# Clock2.net
KiCad netlist of a schematic drawn in EAGLE
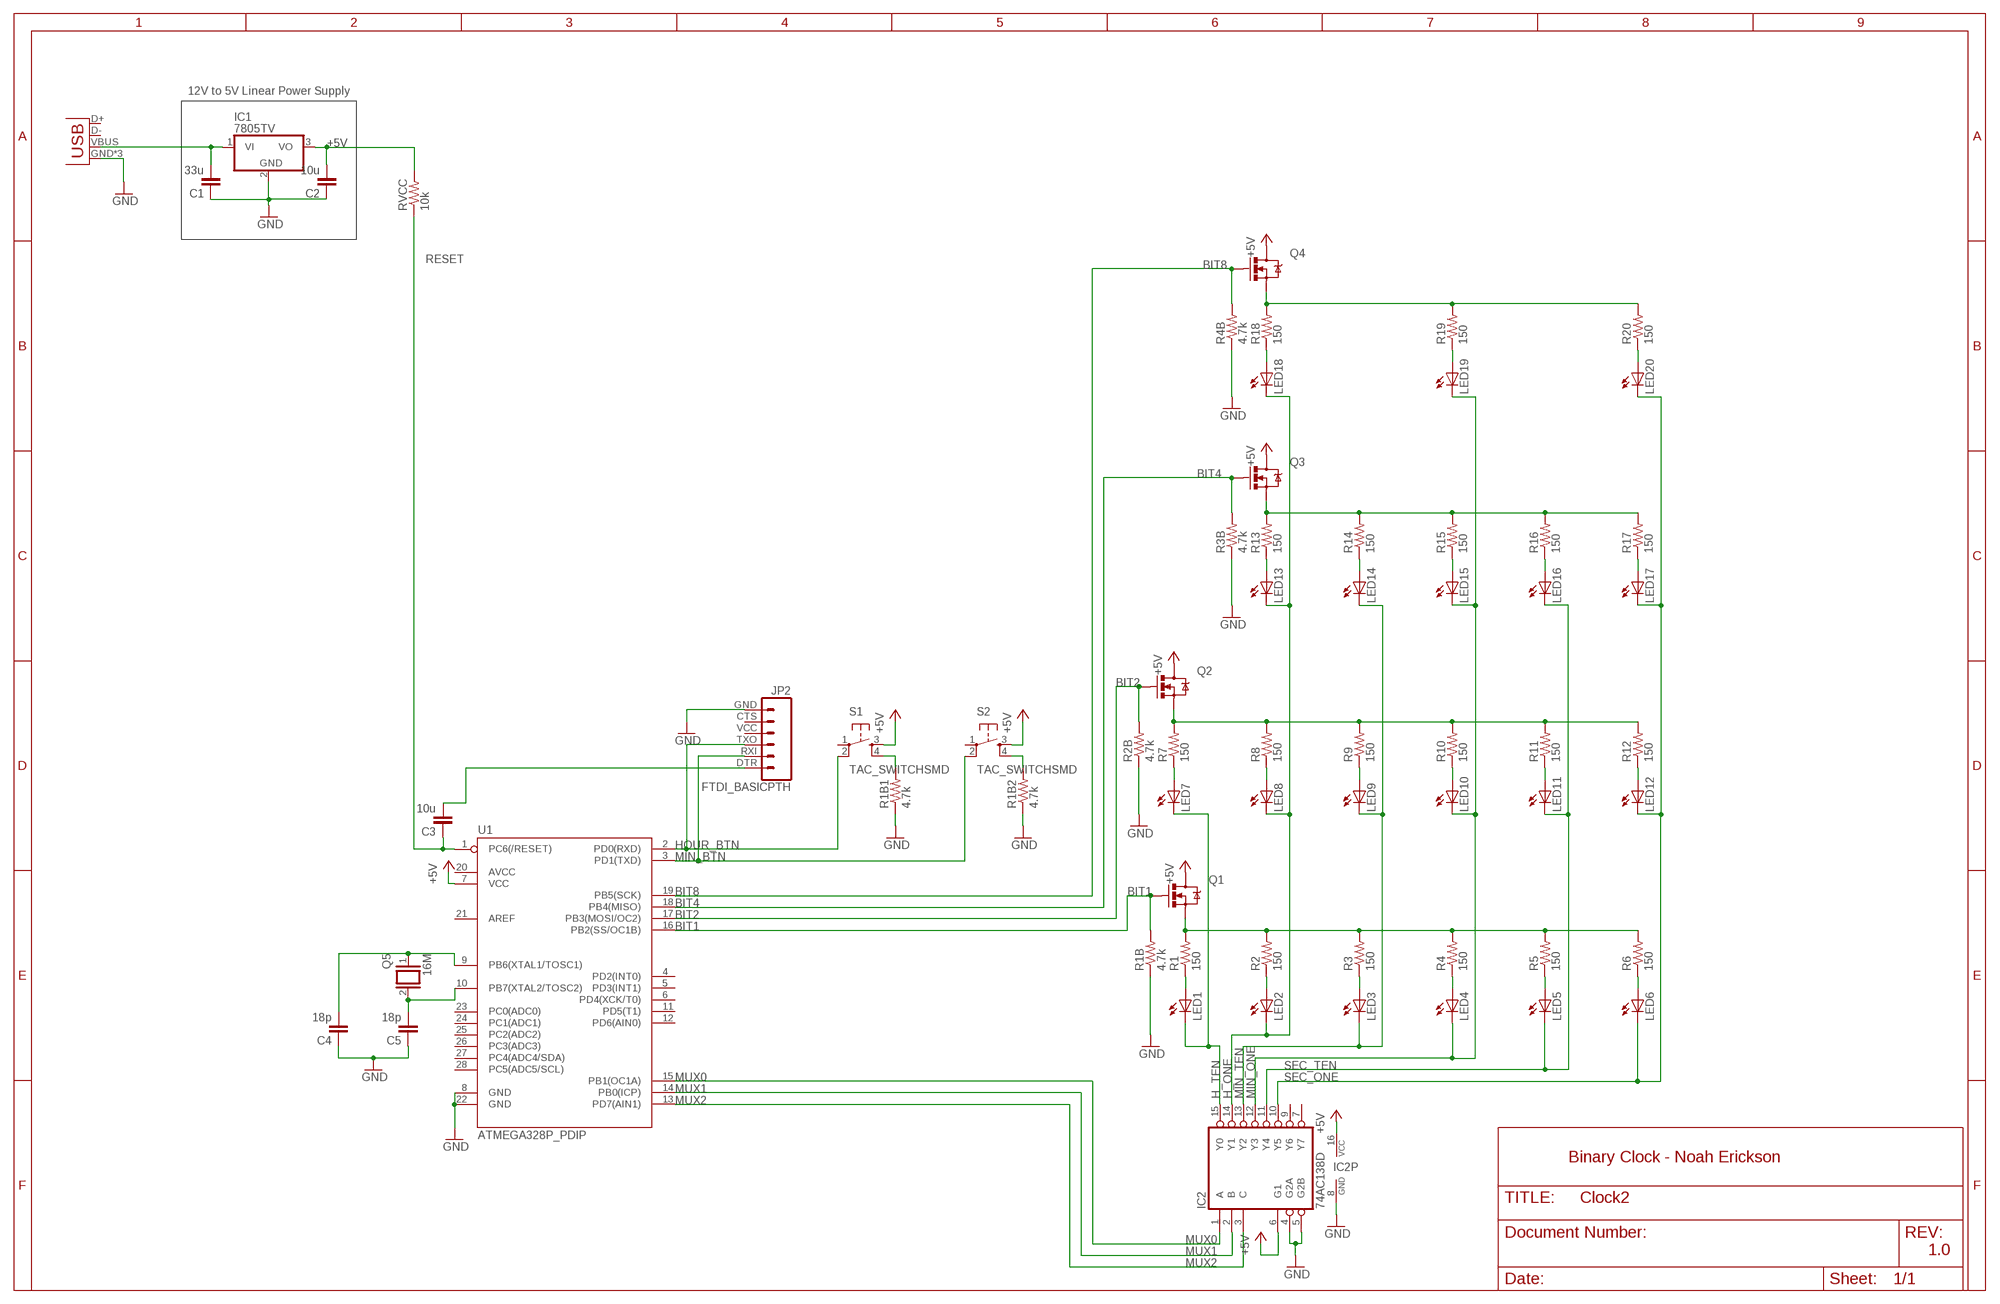
[diagram p0: schematic, sheet 1]

(export (version "E")
  (design (tool "Eeschema 10.0.6"))
  (components
    (comp (ref "C1")
      (value "33u")
      (footprint "eagle-import:C1206")
      (libsource (lib "eagle-import") (part "C-EUC1206"))
    )
    (comp (ref "C2")
      (value "10u")
      (footprint "eagle-import:C1206")
      (libsource (lib "eagle-import") (part "C-EUC1206"))
    )
    (comp (ref "C3")
      (value "10u")
      (footprint "eagle-import:C1206")
      (libsource (lib "eagle-import") (part "C-EUC1206"))
    )
    (comp (ref "C4")
      (value "18p")
      (footprint "eagle-import:C1206")
      (libsource (lib "eagle-import") (part "C-EUC1206"))
    )
    (comp (ref "C5")
      (value "18p")
      (footprint "eagle-import:C1206")
      (libsource (lib "eagle-import") (part "C-EUC1206"))
    )
    (comp (ref "IC1")
      (value "7805TV")
      (footprint "eagle-import:TO220V")
      (libsource (lib "eagle-import") (part "78TV05"))
    )
    (comp (ref "IC2")
      (value "74AC138D")
      (footprint "eagle-import:SO16")
      (libsource (lib "eagle-import") (part "74138DAC"))
    )
    (comp (ref "JP1")
      (value "USB-MICROB")
      (footprint "eagle-import:USB-MICROB")
      (libsource (lib "eagle-import") (part "USB-MICROB"))
    )
    (comp (ref "JP2")
      (value "FTDI_BASICPTH")
      (footprint "eagle-import:FTDI_BASIC")
      (libsource (lib "eagle-import") (part "FTDI_BASICPTH"))
    )
    (comp (ref "LED1")
      (value "LED3MM")
      (footprint "eagle-import:LED3MM")
      (libsource (lib "eagle-import") (part "LED3MM"))
    )
    (comp (ref "LED2")
      (value "LED3MM")
      (footprint "eagle-import:LED3MM")
      (libsource (lib "eagle-import") (part "LED3MM"))
    )
    (comp (ref "LED3")
      (value "LED3MM")
      (footprint "eagle-import:LED3MM")
      (libsource (lib "eagle-import") (part "LED3MM"))
    )
    (comp (ref "LED4")
      (value "LED3MM")
      (footprint "eagle-import:LED3MM")
      (libsource (lib "eagle-import") (part "LED3MM"))
    )
    (comp (ref "LED5")
      (value "LED3MM")
      (footprint "eagle-import:LED3MM")
      (libsource (lib "eagle-import") (part "LED3MM"))
    )
    (comp (ref "LED6")
      (value "LED3MM")
      (footprint "eagle-import:LED3MM")
      (libsource (lib "eagle-import") (part "LED3MM"))
    )
    (comp (ref "LED7")
      (value "LED3MM")
      (footprint "eagle-import:LED3MM")
      (libsource (lib "eagle-import") (part "LED3MM"))
    )
    (comp (ref "LED8")
      (value "LED3MM")
      (footprint "eagle-import:LED3MM")
      (libsource (lib "eagle-import") (part "LED3MM"))
    )
    (comp (ref "LED9")
      (value "LED3MM")
      (footprint "eagle-import:LED3MM")
      (libsource (lib "eagle-import") (part "LED3MM"))
    )
    (comp (ref "LED10")
      (value "LED3MM")
      (footprint "eagle-import:LED3MM")
      (libsource (lib "eagle-import") (part "LED3MM"))
    )
    (comp (ref "LED11")
      (value "LED3MM")
      (footprint "eagle-import:LED3MM")
      (libsource (lib "eagle-import") (part "LED3MM"))
    )
    (comp (ref "LED12")
      (value "LED3MM")
      (footprint "eagle-import:LED3MM")
      (libsource (lib "eagle-import") (part "LED3MM"))
    )
    (comp (ref "LED13")
      (value "LED3MM")
      (footprint "eagle-import:LED3MM")
      (libsource (lib "eagle-import") (part "LED3MM"))
    )
    (comp (ref "LED14")
      (value "LED3MM")
      (footprint "eagle-import:LED3MM")
      (libsource (lib "eagle-import") (part "LED3MM"))
    )
    (comp (ref "LED15")
      (value "LED3MM")
      (footprint "eagle-import:LED3MM")
      (libsource (lib "eagle-import") (part "LED3MM"))
    )
    (comp (ref "LED16")
      (value "LED3MM")
      (footprint "eagle-import:LED3MM")
      (libsource (lib "eagle-import") (part "LED3MM"))
    )
    (comp (ref "LED17")
      (value "LED3MM")
      (footprint "eagle-import:LED3MM")
      (libsource (lib "eagle-import") (part "LED3MM"))
    )
    (comp (ref "LED18")
      (value "LED3MM")
      (footprint "eagle-import:LED3MM")
      (libsource (lib "eagle-import") (part "LED3MM"))
    )
    (comp (ref "LED19")
      (value "LED3MM")
      (footprint "eagle-import:LED3MM")
      (libsource (lib "eagle-import") (part "LED3MM"))
    )
    (comp (ref "LED20")
      (value "LED3MM")
      (footprint "eagle-import:LED3MM")
      (libsource (lib "eagle-import") (part "LED3MM"))
    )
    (comp (ref "Q1")
      (value "MOSFET-NCHANNELBSS138")
      (footprint "eagle-import:SOT23-3")
      (libsource (lib "eagle-import") (part "MOSFET-NCHANNELBSS138"))
    )
    (comp (ref "Q2")
      (value "MOSFET-NCHANNELBSS138")
      (footprint "eagle-import:SOT23-3")
      (libsource (lib "eagle-import") (part "MOSFET-NCHANNELBSS138"))
    )
    (comp (ref "Q3")
      (value "MOSFET-NCHANNELBSS138")
      (footprint "eagle-import:SOT23-3")
      (libsource (lib "eagle-import") (part "MOSFET-NCHANNELBSS138"))
    )
    (comp (ref "Q4")
      (value "MOSFET-NCHANNELBSS138")
      (footprint "eagle-import:SOT23-3")
      (libsource (lib "eagle-import") (part "MOSFET-NCHANNELBSS138"))
    )
    (comp (ref "Q5")
      (value "16M")
      (footprint "eagle-import:QS")
      (libsource (lib "eagle-import") (part "XTAL/S"))
    )
    (comp (ref "R1")
      (value "150")
      (footprint "eagle-import:R1206")
      (libsource (lib "eagle-import") (part "R-US_R1206"))
    )
    (comp (ref "R1B")
      (value "4.7k")
      (footprint "eagle-import:R1206")
      (libsource (lib "eagle-import") (part "R-US_R1206"))
    )
    (comp (ref "R1B1")
      (value "4.7k")
      (footprint "eagle-import:R1206")
      (libsource (lib "eagle-import") (part "R-US_R1206"))
    )
    (comp (ref "R1B2")
      (value "4.7k")
      (footprint "eagle-import:R1206")
      (libsource (lib "eagle-import") (part "R-US_R1206"))
    )
    (comp (ref "R2")
      (value "150")
      (footprint "eagle-import:R1206")
      (libsource (lib "eagle-import") (part "R-US_R1206"))
    )
    (comp (ref "R2B")
      (value "4.7k")
      (footprint "eagle-import:R1206")
      (libsource (lib "eagle-import") (part "R-US_R1206"))
    )
    (comp (ref "R3")
      (value "150")
      (footprint "eagle-import:R1206")
      (libsource (lib "eagle-import") (part "R-US_R1206"))
    )
    (comp (ref "R3B")
      (value "4.7k")
      (footprint "eagle-import:R1206")
      (libsource (lib "eagle-import") (part "R-US_R1206"))
    )
    (comp (ref "R4")
      (value "150")
      (footprint "eagle-import:R1206")
      (libsource (lib "eagle-import") (part "R-US_R1206"))
    )
    (comp (ref "R4B")
      (value "4.7k")
      (footprint "eagle-import:R1206")
      (libsource (lib "eagle-import") (part "R-US_R1206"))
    )
    (comp (ref "R5")
      (value "150")
      (footprint "eagle-import:R1206")
      (libsource (lib "eagle-import") (part "R-US_R1206"))
    )
    (comp (ref "R6")
      (value "150")
      (footprint "eagle-import:R1206")
      (libsource (lib "eagle-import") (part "R-US_R1206"))
    )
    (comp (ref "R7")
      (value "150")
      (footprint "eagle-import:R1206")
      (libsource (lib "eagle-import") (part "R-US_R1206"))
    )
    (comp (ref "R8")
      (value "150")
      (footprint "eagle-import:R1206")
      (libsource (lib "eagle-import") (part "R-US_R1206"))
    )
    (comp (ref "R9")
      (value "150")
      (footprint "eagle-import:R1206")
      (libsource (lib "eagle-import") (part "R-US_R1206"))
    )
    (comp (ref "R10")
      (value "150")
      (footprint "eagle-import:R1206")
      (libsource (lib "eagle-import") (part "R-US_R1206"))
    )
    (comp (ref "R11")
      (value "150")
      (footprint "eagle-import:R1206")
      (libsource (lib "eagle-import") (part "R-US_R1206"))
    )
    (comp (ref "R12")
      (value "150")
      (footprint "eagle-import:R1206")
      (libsource (lib "eagle-import") (part "R-US_R1206"))
    )
    (comp (ref "R13")
      (value "150")
      (footprint "eagle-import:R1206")
      (libsource (lib "eagle-import") (part "R-US_R1206"))
    )
    (comp (ref "R14")
      (value "150")
      (footprint "eagle-import:R1206")
      (libsource (lib "eagle-import") (part "R-US_R1206"))
    )
    (comp (ref "R15")
      (value "150")
      (footprint "eagle-import:R1206")
      (libsource (lib "eagle-import") (part "R-US_R1206"))
    )
    (comp (ref "R16")
      (value "150")
      (footprint "eagle-import:R1206")
      (libsource (lib "eagle-import") (part "R-US_R1206"))
    )
    (comp (ref "R17")
      (value "150")
      (footprint "eagle-import:R1206")
      (libsource (lib "eagle-import") (part "R-US_R1206"))
    )
    (comp (ref "R18")
      (value "150")
      (footprint "eagle-import:R1206")
      (libsource (lib "eagle-import") (part "R-US_R1206"))
    )
    (comp (ref "R19")
      (value "150")
      (footprint "eagle-import:R1206")
      (libsource (lib "eagle-import") (part "R-US_R1206"))
    )
    (comp (ref "R20")
      (value "150")
      (footprint "eagle-import:R1206")
      (libsource (lib "eagle-import") (part "R-US_R1206"))
    )
    (comp (ref "RVCC")
      (value "10k")
      (footprint "eagle-import:R1206")
      (libsource (lib "eagle-import") (part "R-US_R1206"))
    )
    (comp (ref "S1")
      (value "TAC_SWITCHSMD")
      (footprint "eagle-import:TACTILE-SWITCH-SMD")
      (libsource (lib "eagle-import") (part "TAC_SWITCHSMD"))
    )
    (comp (ref "S2")
      (value "TAC_SWITCHSMD")
      (footprint "eagle-import:TACTILE-SWITCH-SMD")
      (libsource (lib "eagle-import") (part "TAC_SWITCHSMD"))
    )
    (comp (ref "U1")
      (value "ATMEGA328P_PDIP")
      (footprint "eagle-import:DIL28-3")
      (libsource (lib "eagle-import") (part "ATMEGA328P_PDIP"))
    )
  )
  (nets
    (net (code "1") (name "+5V") (class "Default")
      (node (ref "C2") (pin "2") (pinfunction "2_2") (pintype "passive"))
      (node (ref "IC1") (pin "3") (pinfunction "VO_3") (pintype "passive"))
      (node (ref "IC2") (pin "16") (pinfunction "VCC_16") (pintype "power_in"))
      (node (ref "IC2") (pin "6") (pinfunction "G1_6") (pintype "input"))
      (node (ref "Q1") (pin "3") (pinfunction "D_3") (pintype "passive"))
      (node (ref "Q2") (pin "3") (pinfunction "D_3") (pintype "passive"))
      (node (ref "Q3") (pin "3") (pinfunction "D_3") (pintype "passive"))
      (node (ref "Q4") (pin "3") (pinfunction "D_3") (pintype "passive"))
      (node (ref "RVCC") (pin "2") (pinfunction "2_2") (pintype "passive"))
      (node (ref "S1") (pin "3") (pinfunction "3_3") (pintype "passive"))
      (node (ref "S2") (pin "3") (pinfunction "3_3") (pintype "passive"))
      (node (ref "U1") (pin "7") (pinfunction "VCC_7") (pintype "bidirectional"))
    )
    (net (code "2") (name "/BIT1") (class "Default")
      (node (ref "Q1") (pin "1") (pinfunction "G_1") (pintype "passive"))
      (node (ref "R1B") (pin "2") (pinfunction "2_2") (pintype "passive"))
      (node (ref "U1") (pin "16") (pinfunction "PB2(SS/OC1B)_16") (pintype "bidirectional"))
    )
    (net (code "3") (name "/BIT2") (class "Default")
      (node (ref "Q2") (pin "1") (pinfunction "G_1") (pintype "passive"))
      (node (ref "R2B") (pin "2") (pinfunction "2_2") (pintype "passive"))
      (node (ref "U1") (pin "17") (pinfunction "PB3(MOSI/OC2)_17") (pintype "bidirectional"))
    )
    (net (code "4") (name "/BIT4") (class "Default")
      (node (ref "Q3") (pin "1") (pinfunction "G_1") (pintype "passive"))
      (node (ref "R3B") (pin "2") (pinfunction "2_2") (pintype "passive"))
      (node (ref "U1") (pin "18") (pinfunction "PB4(MISO)_18") (pintype "bidirectional"))
    )
    (net (code "5") (name "/BIT8") (class "Default")
      (node (ref "Q4") (pin "1") (pinfunction "G_1") (pintype "passive"))
      (node (ref "R4B") (pin "2") (pinfunction "2_2") (pintype "passive"))
      (node (ref "U1") (pin "19") (pinfunction "PB5(SCK)_19") (pintype "bidirectional"))
    )
    (net (code "6") (name "/HOUR_BTN") (class "Default")
      (node (ref "JP2") (pin "TXO") (pinfunction "3_TXO") (pintype "passive"))
      (node (ref "S1") (pin "2") (pinfunction "2_2") (pintype "passive"))
      (node (ref "U1") (pin "2") (pinfunction "PD0(RXD)_2") (pintype "bidirectional"))
    )
    (net (code "7") (name "/H_ONE") (class "Default")
      (node (ref "IC2") (pin "14") (pinfunction "Y1_14") (pintype "output"))
      (node (ref "LED13") (pin "K") (pinfunction "C_K") (pintype "passive"))
      (node (ref "LED18") (pin "K") (pinfunction "C_K") (pintype "passive"))
      (node (ref "LED2") (pin "K") (pinfunction "C_K") (pintype "passive"))
      (node (ref "LED8") (pin "K") (pinfunction "C_K") (pintype "passive"))
    )
    (net (code "8") (name "/H_TEN") (class "Default")
      (node (ref "IC2") (pin "15") (pinfunction "Y0_15") (pintype "output"))
      (node (ref "LED1") (pin "K") (pinfunction "C_K") (pintype "passive"))
      (node (ref "LED7") (pin "K") (pinfunction "C_K") (pintype "passive"))
    )
    (net (code "9") (name "/MIN_BTN") (class "Default")
      (node (ref "JP2") (pin "RXI") (pinfunction "2_RXI") (pintype "passive"))
      (node (ref "S2") (pin "2") (pinfunction "2_2") (pintype "passive"))
      (node (ref "U1") (pin "3") (pinfunction "PD1(TXD)_3") (pintype "bidirectional"))
    )
    (net (code "10") (name "/MIN_ONE") (class "Default")
      (node (ref "IC2") (pin "12") (pinfunction "Y3_12") (pintype "output"))
      (node (ref "LED10") (pin "K") (pinfunction "C_K") (pintype "passive"))
      (node (ref "LED15") (pin "K") (pinfunction "C_K") (pintype "passive"))
      (node (ref "LED19") (pin "K") (pinfunction "C_K") (pintype "passive"))
      (node (ref "LED4") (pin "K") (pinfunction "C_K") (pintype "passive"))
    )
    (net (code "11") (name "/MIN_TEN") (class "Default")
      (node (ref "IC2") (pin "13") (pinfunction "Y2_13") (pintype "output"))
      (node (ref "LED14") (pin "K") (pinfunction "C_K") (pintype "passive"))
      (node (ref "LED3") (pin "K") (pinfunction "C_K") (pintype "passive"))
      (node (ref "LED9") (pin "K") (pinfunction "C_K") (pintype "passive"))
    )
    (net (code "12") (name "/MUX0") (class "Default")
      (node (ref "IC2") (pin "1") (pinfunction "A_1") (pintype "input"))
      (node (ref "U1") (pin "15") (pinfunction "PB1(OC1A)_15") (pintype "bidirectional"))
    )
    (net (code "13") (name "/MUX1") (class "Default")
      (node (ref "IC2") (pin "2") (pinfunction "B_2") (pintype "input"))
      (node (ref "U1") (pin "14") (pinfunction "PB0(ICP)_14") (pintype "bidirectional"))
    )
    (net (code "14") (name "/MUX2") (class "Default")
      (node (ref "IC2") (pin "3") (pinfunction "C_3") (pintype "input"))
      (node (ref "U1") (pin "13") (pinfunction "PD7(AIN1)_13") (pintype "bidirectional"))
    )
    (net (code "15") (name "/RESET") (class "Default")
      (node (ref "C3") (pin "1") (pinfunction "1_1") (pintype "passive"))
      (node (ref "RVCC") (pin "1") (pinfunction "1_1") (pintype "passive"))
      (node (ref "U1") (pin "1") (pinfunction "PC6(/RESET)_1") (pintype "bidirectional"))
    )
    (net (code "16") (name "/SEC_ONE") (class "Default")
      (node (ref "IC2") (pin "10") (pinfunction "Y5_10") (pintype "output"))
      (node (ref "LED12") (pin "K") (pinfunction "C_K") (pintype "passive"))
      (node (ref "LED17") (pin "K") (pinfunction "C_K") (pintype "passive"))
      (node (ref "LED20") (pin "K") (pinfunction "C_K") (pintype "passive"))
      (node (ref "LED6") (pin "K") (pinfunction "C_K") (pintype "passive"))
    )
    (net (code "17") (name "/SEC_TEN") (class "Default")
      (node (ref "IC2") (pin "11") (pinfunction "Y4_11") (pintype "output"))
      (node (ref "LED11") (pin "K") (pinfunction "C_K") (pintype "passive"))
      (node (ref "LED16") (pin "K") (pinfunction "C_K") (pintype "passive"))
      (node (ref "LED5") (pin "K") (pinfunction "C_K") (pintype "passive"))
    )
    (net (code "18") (name "GND") (class "Default")
      (node (ref "C1") (pin "1") (pinfunction "1_1") (pintype "passive"))
      (node (ref "C2") (pin "1") (pinfunction "1_1") (pintype "passive"))
      (node (ref "C4") (pin "1") (pinfunction "1_1") (pintype "passive"))
      (node (ref "C5") (pin "1") (pinfunction "1_1") (pintype "passive"))
      (node (ref "IC1") (pin "2") (pinfunction "GND_2") (pintype "passive"))
      (node (ref "IC2") (pin "4") (pinfunction "G2A_4") (pintype "input"))
      (node (ref "IC2") (pin "5") (pinfunction "G2B_5") (pintype "input"))
      (node (ref "IC2") (pin "8") (pinfunction "GND_8") (pintype "power_in"))
      (node (ref "JP1") (pin "GND") (pinfunction "GND_GND") (pintype "bidirectional"))
      (node (ref "JP1") (pin "MT1") (pinfunction "GND_MT1") (pintype "bidirectional"))
      (node (ref "JP1") (pin "MT2") (pinfunction "GND_MT2") (pintype "bidirectional"))
      (node (ref "JP2") (pin "GND") (pinfunction "6_GND") (pintype "passive"))
      (node (ref "R1B") (pin "1") (pinfunction "1_1") (pintype "passive"))
      (node (ref "R1B1") (pin "1") (pinfunction "1_1") (pintype "passive"))
      (node (ref "R1B2") (pin "1") (pinfunction "1_1") (pintype "passive"))
      (node (ref "R2B") (pin "1") (pinfunction "1_1") (pintype "passive"))
      (node (ref "R3B") (pin "1") (pinfunction "1_1") (pintype "passive"))
      (node (ref "R4B") (pin "1") (pinfunction "1_1") (pintype "passive"))
      (node (ref "U1") (pin "22") (pinfunction "GND_22") (pintype "bidirectional"))
      (node (ref "U1") (pin "8") (pinfunction "GND_8") (pintype "bidirectional"))
    )
    (net (code "19") (name "Net-(IC1-VI)") (class "Default")
      (node (ref "C1") (pin "2") (pinfunction "2_2") (pintype "passive"))
      (node (ref "IC1") (pin "1") (pinfunction "VI_1") (pintype "input"))
      (node (ref "JP1") (pin "VBUS") (pinfunction "VBUS_VBUS") (pintype "bidirectional"))
    )
    (net (code "20") (name "Net-(JP2-1)") (class "Default")
      (node (ref "C3") (pin "2") (pinfunction "2_2") (pintype "passive"))
      (node (ref "JP2") (pin "DTR") (pinfunction "1_DTR") (pintype "passive"))
    )
    (net (code "21") (name "Net-(LED1-PadA)") (class "Default")
      (node (ref "LED1") (pin "A") (pinfunction "A_A") (pintype "passive"))
      (node (ref "R1") (pin "1") (pinfunction "1_1") (pintype "passive"))
    )
    (net (code "22") (name "Net-(LED2-PadA)") (class "Default")
      (node (ref "LED2") (pin "A") (pinfunction "A_A") (pintype "passive"))
      (node (ref "R2") (pin "1") (pinfunction "1_1") (pintype "passive"))
    )
    (net (code "23") (name "Net-(LED3-PadA)") (class "Default")
      (node (ref "LED3") (pin "A") (pinfunction "A_A") (pintype "passive"))
      (node (ref "R3") (pin "1") (pinfunction "1_1") (pintype "passive"))
    )
    (net (code "24") (name "Net-(LED4-PadA)") (class "Default")
      (node (ref "LED4") (pin "A") (pinfunction "A_A") (pintype "passive"))
      (node (ref "R4") (pin "1") (pinfunction "1_1") (pintype "passive"))
    )
    (net (code "25") (name "Net-(LED5-PadA)") (class "Default")
      (node (ref "LED5") (pin "A") (pinfunction "A_A") (pintype "passive"))
      (node (ref "R5") (pin "1") (pinfunction "1_1") (pintype "passive"))
    )
    (net (code "26") (name "Net-(LED6-PadA)") (class "Default")
      (node (ref "LED6") (pin "A") (pinfunction "A_A") (pintype "passive"))
      (node (ref "R6") (pin "1") (pinfunction "1_1") (pintype "passive"))
    )
    (net (code "27") (name "Net-(LED7-PadA)") (class "Default")
      (node (ref "LED7") (pin "A") (pinfunction "A_A") (pintype "passive"))
      (node (ref "R7") (pin "1") (pinfunction "1_1") (pintype "passive"))
    )
    (net (code "28") (name "Net-(LED8-PadA)") (class "Default")
      (node (ref "LED8") (pin "A") (pinfunction "A_A") (pintype "passive"))
      (node (ref "R8") (pin "1") (pinfunction "1_1") (pintype "passive"))
    )
    (net (code "29") (name "Net-(LED9-PadA)") (class "Default")
      (node (ref "LED9") (pin "A") (pinfunction "A_A") (pintype "passive"))
      (node (ref "R9") (pin "1") (pinfunction "1_1") (pintype "passive"))
    )
    (net (code "30") (name "Net-(LED10-PadA)") (class "Default")
      (node (ref "LED10") (pin "A") (pinfunction "A_A") (pintype "passive"))
      (node (ref "R10") (pin "1") (pinfunction "1_1") (pintype "passive"))
    )
    (net (code "31") (name "Net-(LED11-PadA)") (class "Default")
      (node (ref "LED11") (pin "A") (pinfunction "A_A") (pintype "passive"))
      (node (ref "R11") (pin "1") (pinfunction "1_1") (pintype "passive"))
    )
    (net (code "32") (name "Net-(LED12-PadA)") (class "Default")
      (node (ref "LED12") (pin "A") (pinfunction "A_A") (pintype "passive"))
      (node (ref "R12") (pin "1") (pinfunction "1_1") (pintype "passive"))
    )
    (net (code "33") (name "Net-(LED13-PadA)") (class "Default")
      (node (ref "LED13") (pin "A") (pinfunction "A_A") (pintype "passive"))
      (node (ref "R13") (pin "1") (pinfunction "1_1") (pintype "passive"))
    )
    (net (code "34") (name "Net-(LED14-PadA)") (class "Default")
      (node (ref "LED14") (pin "A") (pinfunction "A_A") (pintype "passive"))
      (node (ref "R14") (pin "1") (pinfunction "1_1") (pintype "passive"))
    )
    (net (code "35") (name "Net-(LED15-PadA)") (class "Default")
      (node (ref "LED15") (pin "A") (pinfunction "A_A") (pintype "passive"))
      (node (ref "R15") (pin "1") (pinfunction "1_1") (pintype "passive"))
    )
    (net (code "36") (name "Net-(LED16-PadA)") (class "Default")
      (node (ref "LED16") (pin "A") (pinfunction "A_A") (pintype "passive"))
      (node (ref "R16") (pin "1") (pinfunction "1_1") (pintype "passive"))
    )
    (net (code "37") (name "Net-(LED17-PadA)") (class "Default")
      (node (ref "LED17") (pin "A") (pinfunction "A_A") (pintype "passive"))
      (node (ref "R17") (pin "1") (pinfunction "1_1") (pintype "passive"))
    )
    (net (code "38") (name "Net-(LED18-PadA)") (class "Default")
      (node (ref "LED18") (pin "A") (pinfunction "A_A") (pintype "passive"))
      (node (ref "R18") (pin "1") (pinfunction "1_1") (pintype "passive"))
    )
    (net (code "39") (name "Net-(LED19-PadA)") (class "Default")
      (node (ref "LED19") (pin "A") (pinfunction "A_A") (pintype "passive"))
      (node (ref "R19") (pin "1") (pinfunction "1_1") (pintype "passive"))
    )
    (net (code "40") (name "Net-(LED20-PadA)") (class "Default")
      (node (ref "LED20") (pin "A") (pinfunction "A_A") (pintype "passive"))
      (node (ref "R20") (pin "1") (pinfunction "1_1") (pintype "passive"))
    )
    (net (code "41") (name "Net-(Q1-S)") (class "Default")
      (node (ref "Q1") (pin "2") (pinfunction "S_2") (pintype "passive"))
      (node (ref "R1") (pin "2") (pinfunction "2_2") (pintype "passive"))
      (node (ref "R2") (pin "2") (pinfunction "2_2") (pintype "passive"))
      (node (ref "R3") (pin "2") (pinfunction "2_2") (pintype "passive"))
      (node (ref "R4") (pin "2") (pinfunction "2_2") (pintype "passive"))
      (node (ref "R5") (pin "2") (pinfunction "2_2") (pintype "passive"))
      (node (ref "R6") (pin "2") (pinfunction "2_2") (pintype "passive"))
    )
    (net (code "42") (name "Net-(Q2-S)") (class "Default")
      (node (ref "Q2") (pin "2") (pinfunction "S_2") (pintype "passive"))
      (node (ref "R10") (pin "2") (pinfunction "2_2") (pintype "passive"))
      (node (ref "R11") (pin "2") (pinfunction "2_2") (pintype "passive"))
      (node (ref "R12") (pin "2") (pinfunction "2_2") (pintype "passive"))
      (node (ref "R7") (pin "2") (pinfunction "2_2") (pintype "passive"))
      (node (ref "R8") (pin "2") (pinfunction "2_2") (pintype "passive"))
      (node (ref "R9") (pin "2") (pinfunction "2_2") (pintype "passive"))
    )
    (net (code "43") (name "Net-(Q3-S)") (class "Default")
      (node (ref "Q3") (pin "2") (pinfunction "S_2") (pintype "passive"))
      (node (ref "R13") (pin "2") (pinfunction "2_2") (pintype "passive"))
      (node (ref "R14") (pin "2") (pinfunction "2_2") (pintype "passive"))
      (node (ref "R15") (pin "2") (pinfunction "2_2") (pintype "passive"))
      (node (ref "R16") (pin "2") (pinfunction "2_2") (pintype "passive"))
      (node (ref "R17") (pin "2") (pinfunction "2_2") (pintype "passive"))
    )
    (net (code "44") (name "Net-(Q4-S)") (class "Default")
      (node (ref "Q4") (pin "2") (pinfunction "S_2") (pintype "passive"))
      (node (ref "R18") (pin "2") (pinfunction "2_2") (pintype "passive"))
      (node (ref "R19") (pin "2") (pinfunction "2_2") (pintype "passive"))
      (node (ref "R20") (pin "2") (pinfunction "2_2") (pintype "passive"))
    )
    (net (code "45") (name "Net-(R1B1-Pad2)") (class "Default")
      (node (ref "R1B1") (pin "2") (pinfunction "2_2") (pintype "passive"))
      (node (ref "S1") (pin "4") (pinfunction "4_4") (pintype "passive"))
    )
    (net (code "46") (name "Net-(R1B2-Pad2)") (class "Default")
      (node (ref "R1B2") (pin "2") (pinfunction "2_2") (pintype "passive"))
      (node (ref "S2") (pin "4") (pinfunction "4_4") (pintype "passive"))
    )
    (net (code "47") (name "Net-(U1-PB6(XTAL1{slash}TOSC1))") (class "Default")
      (node (ref "C4") (pin "2") (pinfunction "2_2") (pintype "passive"))
      (node (ref "Q5") (pin "1") (pinfunction "1_1") (pintype "passive"))
      (node (ref "U1") (pin "9") (pinfunction "PB6(XTAL1/TOSC1)_9") (pintype "bidirectional"))
    )
    (net (code "48") (name "Net-(U1-PB7(XTAL2{slash}TOSC2))") (class "Default")
      (node (ref "C5") (pin "2") (pinfunction "2_2") (pintype "passive"))
      (node (ref "Q5") (pin "2") (pinfunction "2_2") (pintype "passive"))
      (node (ref "U1") (pin "10") (pinfunction "PB7(XTAL2/TOSC2)_10") (pintype "bidirectional"))
    )
    (net (code "49") (name "unconnected-(IC2A-Y6-Pad9)") (class "Default")
      (node (ref "IC2") (pin "9") (pinfunction "Y6_9") (pintype "output"))
    )
    (net (code "50") (name "unconnected-(IC2A-Y7-Pad7)") (class "Default")
      (node (ref "IC2") (pin "7") (pinfunction "Y7_7") (pintype "output"))
    )
    (net (code "51") (name "unconnected-(JP1-PadD+)") (class "Default")
      (node (ref "JP1") (pin "D+") (pinfunction "D+_D+") (pintype "bidirectional"))
    )
    (net (code "52") (name "unconnected-(JP1-PadD-)") (class "Default")
      (node (ref "JP1") (pin "D-") (pinfunction "D-_D-") (pintype "bidirectional"))
    )
    (net (code "53") (name "unconnected-(JP2-4-PadVCC)") (class "Default")
      (node (ref "JP2") (pin "VCC") (pinfunction "4_VCC") (pintype "passive"))
    )
    (net (code "54") (name "unconnected-(JP2-5-PadCTS)") (class "Default")
      (node (ref "JP2") (pin "CTS") (pinfunction "5_CTS") (pintype "passive"))
    )
    (net (code "55") (name "unconnected-(S1-Pad1)") (class "Default")
      (node (ref "S1") (pin "1") (pinfunction "1_1") (pintype "passive"))
    )
    (net (code "56") (name "unconnected-(S2-Pad1)") (class "Default")
      (node (ref "S2") (pin "1") (pinfunction "1_1") (pintype "passive"))
    )
    (net (code "57") (name "unconnected-(U1-AREF-Pad21)") (class "Default")
      (node (ref "U1") (pin "21") (pinfunction "AREF_21") (pintype "bidirectional"))
    )
    (net (code "58") (name "unconnected-(U1-AVCC-Pad20)") (class "Default")
      (node (ref "U1") (pin "20") (pinfunction "AVCC_20") (pintype "bidirectional"))
    )
    (net (code "59") (name "unconnected-(U1-PC0(ADC0)-Pad23)") (class "Default")
      (node (ref "U1") (pin "23") (pinfunction "PC0(ADC0)_23") (pintype "bidirectional"))
    )
    (net (code "60") (name "unconnected-(U1-PC1(ADC1)-Pad24)") (class "Default")
      (node (ref "U1") (pin "24") (pinfunction "PC1(ADC1)_24") (pintype "bidirectional"))
    )
    (net (code "61") (name "unconnected-(U1-PC2(ADC2)-Pad25)") (class "Default")
      (node (ref "U1") (pin "25") (pinfunction "PC2(ADC2)_25") (pintype "bidirectional"))
    )
    (net (code "62") (name "unconnected-(U1-PC3(ADC3)-Pad26)") (class "Default")
      (node (ref "U1") (pin "26") (pinfunction "PC3(ADC3)_26") (pintype "bidirectional"))
    )
    (net (code "63") (name "unconnected-(U1-PC4(ADC4{slash}SDA)-Pad27)") (class "Default")
      (node (ref "U1") (pin "27") (pinfunction "PC4(ADC4/SDA)_27") (pintype "bidirectional"))
    )
    (net (code "64") (name "unconnected-(U1-PC5(ADC5{slash}SCL)-Pad28)") (class "Default")
      (node (ref "U1") (pin "28") (pinfunction "PC5(ADC5/SCL)_28") (pintype "bidirectional"))
    )
    (net (code "65") (name "unconnected-(U1-PD2(INT0)-Pad4)") (class "Default")
      (node (ref "U1") (pin "4") (pinfunction "PD2(INT0)_4") (pintype "bidirectional"))
    )
    (net (code "66") (name "unconnected-(U1-PD3(INT1)-Pad5)") (class "Default")
      (node (ref "U1") (pin "5") (pinfunction "PD3(INT1)_5") (pintype "bidirectional"))
    )
    (net (code "67") (name "unconnected-(U1-PD4(XCK{slash}T0)-Pad6)") (class "Default")
      (node (ref "U1") (pin "6") (pinfunction "PD4(XCK/T0)_6") (pintype "bidirectional"))
    )
    (net (code "68") (name "unconnected-(U1-PD5(T1)-Pad11)") (class "Default")
      (node (ref "U1") (pin "11") (pinfunction "PD5(T1)_11") (pintype "bidirectional"))
    )
    (net (code "69") (name "unconnected-(U1-PD6(AIN0)-Pad12)") (class "Default")
      (node (ref "U1") (pin "12") (pinfunction "PD6(AIN0)_12") (pintype "bidirectional"))
    )
  )
)
